# TinUI_v1.net
KiCad netlist of a schematic drawn in EAGLE
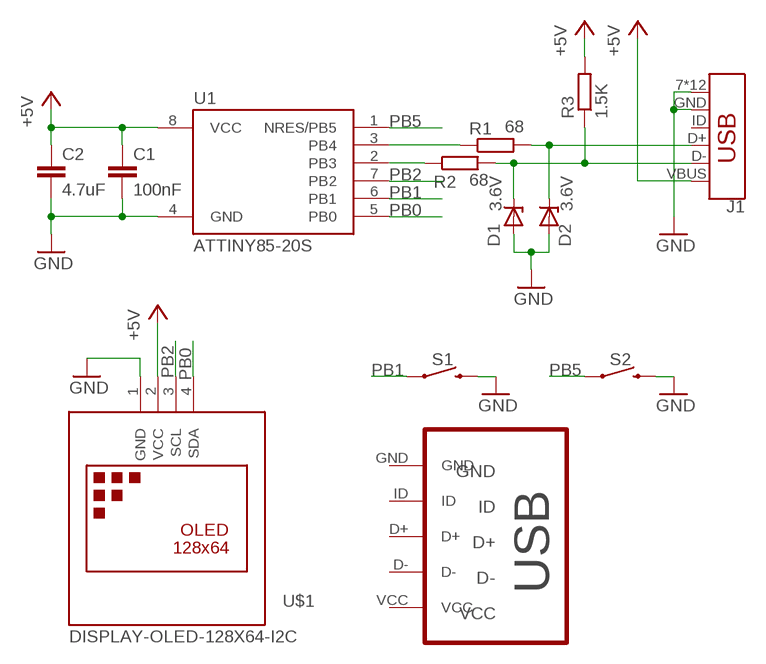
[diagram p0: schematic, sheet 1]

(export (version "E")
  (design (tool "Eeschema 10.0.6"))
  (components
    (comp (ref "C1")
      (value "100nF")
      (footprint "eagle-import:C0603")
      (libsource (lib "eagle-import") (part "C-EUC0603"))
    )
    (comp (ref "C2")
      (value "4.7uF")
      (footprint "eagle-import:C0603")
      (libsource (lib "eagle-import") (part "C-EUC0603"))
    )
    (comp (ref "D1")
      (value "3.6V")
      (footprint "eagle-import:SOD80C")
      (libsource (lib "eagle-import") (part "ZENER-DIODESOD80C"))
    )
    (comp (ref "D2")
      (value "3.6V")
      (footprint "eagle-import:SOD80C")
      (libsource (lib "eagle-import") (part "ZENER-DIODESOD80C"))
    )
    (comp (ref "J1")
      (value "AMP FCI 10103594-0001LF")
      (footprint "eagle-import:USB-MICROB-PTH")
      (libsource (lib "eagle-import") (part "USB_MICRO-B_HALF_PTH"))
    )
    (comp (ref "R1")
      (value "68")
      (footprint "eagle-import:R0603")
      (libsource (lib "eagle-import") (part "R-EU_R0603"))
    )
    (comp (ref "R2")
      (value "68")
      (footprint "eagle-import:R0603")
      (libsource (lib "eagle-import") (part "R-EU_R0603"))
    )
    (comp (ref "R3")
      (value "1.5K")
      (footprint "eagle-import:R0603")
      (libsource (lib "eagle-import") (part "R-EU_R0603"))
    )
    (comp (ref "S1")
      (value "MOMENTARY-SWITCH-SPST-SMD-6.0X3.5MM")
      (footprint "eagle-import:TACTILE_SWITCH_SMD_6.0X3.5MM")
      (libsource (lib "eagle-import") (part "MOMENTARY-SWITCH-SPST-SMD-6.0X3.5MM"))
    )
    (comp (ref "S2")
      (value "MOMENTARY-SWITCH-SPST-SMD-6.0X3.5MM")
      (footprint "eagle-import:TACTILE_SWITCH_SMD_6.0X3.5MM")
      (libsource (lib "eagle-import") (part "MOMENTARY-SWITCH-SPST-SMD-6.0X3.5MM"))
    )
    (comp (ref "U$1")
      (value "DISPLAY-OLED-128X64-I2C")
      (footprint "eagle-import:DISPLAY-OLED-128X64-I2C")
      (libsource (lib "eagle-import") (part "DISPLAY-OLED-128X64-I2C"))
    )
    (comp (ref "U$2")
      (value "MICRO-USB-B")
      (footprint "eagle-import:MICRO_USB_4_LEGS")
      (libsource (lib "eagle-import") (part "MICRO-USB-B"))
    )
    (comp (ref "U1")
      (value "ATTINY85-20S")
      (footprint "eagle-import:SOIC8_EIAJ_208MIL")
      (libsource (lib "eagle-import") (part "ATTINY85S-20"))
    )
  )
  (nets
    (net (code "1") (name "+5V") (class "Default")
      (node (ref "C1") (pin "1") (pinfunction "1_1") (pintype "passive"))
      (node (ref "C2") (pin "1") (pinfunction "1_1") (pintype "passive"))
      (node (ref "J1") (pin "VBUS") (pinfunction "VBUS_VBUS") (pintype "power_in"))
      (node (ref "R3") (pin "2") (pinfunction "2_2") (pintype "passive"))
      (node (ref "U$1") (pin "2") (pinfunction "VCC_2") (pintype "power_in"))
      (node (ref "U1") (pin "8") (pinfunction "VCC_8") (pintype "power_in"))
    )
    (net (code "2") (name "/PB0") (class "Default")
      (node (ref "U$1") (pin "4") (pinfunction "SDA_4") (pintype "bidirectional"))
      (node (ref "U1") (pin "5") (pinfunction "PB0_5") (pintype "bidirectional"))
    )
    (net (code "3") (name "/PB1") (class "Default")
      (node (ref "S1") (pin "1") (pinfunction "1_1") (pintype "passive"))
      (node (ref "U1") (pin "6") (pinfunction "PB1_6") (pintype "bidirectional"))
    )
    (net (code "4") (name "/PB2") (class "Default")
      (node (ref "U$1") (pin "3") (pinfunction "SCL_3") (pintype "bidirectional"))
      (node (ref "U1") (pin "7") (pinfunction "PB2_7") (pintype "bidirectional"))
    )
    (net (code "5") (name "/PB5") (class "Default")
      (node (ref "S2") (pin "1") (pinfunction "1_1") (pintype "passive"))
      (node (ref "U1") (pin "1") (pinfunction "NRES/PB5_1") (pintype "bidirectional"))
    )
    (net (code "6") (name "GND") (class "Default")
      (node (ref "C1") (pin "2") (pinfunction "2_2") (pintype "passive"))
      (node (ref "C2") (pin "2") (pinfunction "2_2") (pintype "passive"))
      (node (ref "D1") (pin "A") (pinfunction "A_A") (pintype "passive"))
      (node (ref "D2") (pin "A") (pinfunction "A_A") (pintype "passive"))
      (node (ref "J1") (pin "7") (pinfunction "SHIELD_7") (pintype "bidirectional"))
      (node (ref "J1") (pin "GND") (pinfunction "GND_GND") (pintype "power_in"))
      (node (ref "J1") (pin "SHEILD2") (pinfunction "SHIELD_SHEILD2") (pintype "bidirectional"))
      (node (ref "J1") (pin "SHIELD") (pinfunction "SHIELD_SHIELD") (pintype "bidirectional"))
      (node (ref "J1") (pin "SHIELD10") (pinfunction "SHIELD_SHIELD10") (pintype "bidirectional"))
      (node (ref "J1") (pin "SHIELD11") (pinfunction "SHIELD_SHIELD11") (pintype "bidirectional"))
      (node (ref "J1") (pin "SHIELD12") (pinfunction "SHIELD_SHIELD12") (pintype "bidirectional"))
      (node (ref "J1") (pin "SHIELD3") (pinfunction "SHIELD_SHIELD3") (pintype "bidirectional"))
      (node (ref "J1") (pin "SHIELD4") (pinfunction "SHIELD_SHIELD4") (pintype "bidirectional"))
      (node (ref "J1") (pin "SHIELD5") (pinfunction "SHIELD_SHIELD5") (pintype "bidirectional"))
      (node (ref "J1") (pin "SHIELD6") (pinfunction "SHIELD_SHIELD6") (pintype "bidirectional"))
      (node (ref "J1") (pin "SHIELD8") (pinfunction "SHIELD_SHIELD8") (pintype "bidirectional"))
      (node (ref "J1") (pin "SHIELD9") (pinfunction "SHIELD_SHIELD9") (pintype "bidirectional"))
      (node (ref "S1") (pin "2") (pinfunction "2_2") (pintype "passive"))
      (node (ref "S2") (pin "2") (pinfunction "2_2") (pintype "passive"))
      (node (ref "U$1") (pin "1") (pinfunction "GND_1") (pintype "power_in"))
      (node (ref "U1") (pin "4") (pinfunction "GND_4") (pintype "power_in"))
    )
    (net (code "7") (name "Net-(D1-PadC)") (class "Default")
      (node (ref "D1") (pin "C") (pinfunction "C_C") (pintype "passive"))
      (node (ref "J1") (pin "D-") (pinfunction "D-_D-") (pintype "bidirectional"))
      (node (ref "R2") (pin "2") (pinfunction "2_2") (pintype "passive"))
      (node (ref "R3") (pin "1") (pinfunction "1_1") (pintype "passive"))
    )
    (net (code "8") (name "Net-(D2-PadC)") (class "Default")
      (node (ref "D2") (pin "C") (pinfunction "C_C") (pintype "passive"))
      (node (ref "J1") (pin "D+") (pinfunction "D+_D+") (pintype "bidirectional"))
      (node (ref "R1") (pin "2") (pinfunction "2_2") (pintype "passive"))
    )
    (net (code "9") (name "Net-(U1-PB3)") (class "Default")
      (node (ref "R2") (pin "1") (pinfunction "1_1") (pintype "passive"))
      (node (ref "U1") (pin "2") (pinfunction "PB3_2") (pintype "bidirectional"))
    )
    (net (code "10") (name "Net-(U1-PB4)") (class "Default")
      (node (ref "R1") (pin "1") (pinfunction "1_1") (pintype "passive"))
      (node (ref "U1") (pin "3") (pinfunction "PB4_3") (pintype "bidirectional"))
    )
    (net (code "11") (name "unconnected-(J1-PadID)") (class "Default")
      (node (ref "J1") (pin "ID") (pinfunction "ID_ID") (pintype "bidirectional"))
    )
    (net (code "12") (name "unconnected-(U$2-PadD+)") (class "Default")
      (node (ref "U$2") (pin "D+") (pinfunction "D+_D+") (pintype "bidirectional"))
    )
    (net (code "13") (name "unconnected-(U$2-PadD-)") (class "Default")
      (node (ref "U$2") (pin "D-") (pinfunction "D-_D-") (pintype "bidirectional"))
    )
    (net (code "14") (name "unconnected-(U$2-PadGND)") (class "Default")
      (node (ref "U$2") (pin "GND") (pinfunction "GND_GND") (pintype "bidirectional"))
    )
    (net (code "15") (name "unconnected-(U$2-PadID)") (class "Default")
      (node (ref "U$2") (pin "ID") (pinfunction "ID_ID") (pintype "bidirectional"))
    )
    (net (code "16") (name "unconnected-(U$2-PadVCC)") (class "Default")
      (node (ref "U$2") (pin "VCC") (pinfunction "VCC_VCC") (pintype "bidirectional"))
    )
  )
)
